# i2c_pullups.net
KiCad netlist of a schematic drawn in Altium Designer
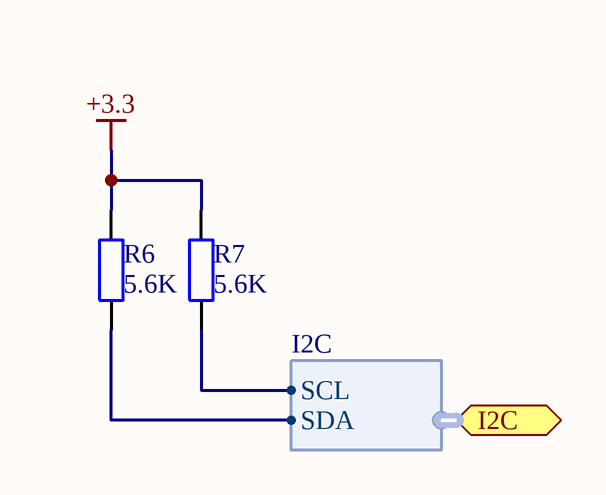
[diagram p0: i2c pullups.SchDoc]

(export (version "E")
  (design (tool "Eeschema 10.0.6"))
  (components
    (comp (ref "R6")
      (value "5.6K")
      (footprint "R0603")
      (description "Resistor")
      (fields (field (name "Comment") "Res2") (field (name "PUBLISHER") "Altium Limited"))
      (libsource (lib "Miscellaneous Devices") (part "Res2"))
    )
    (comp (ref "R7")
      (value "5.6K")
      (footprint "R0603")
      (description "Resistor")
      (fields (field (name "Comment") "Res2") (field (name "PUBLISHER") "Altium Limited"))
      (libsource (lib "Miscellaneous Devices") (part "Res2"))
    )
  )
  (nets
    (net (code "2") (name "+3.3") (class "Default")
      (node (ref "R6") (pin "2") (pinfunction "2_2") (pintype "passive"))
      (node (ref "R7") (pin "2") (pinfunction "2_2") (pintype "passive"))
    )
    (net (code "3") (name "/SCL") (class "Default")
      (node (ref "R7") (pin "1") (pinfunction "1_1") (pintype "passive"))
    )
    (net (code "4") (name "/SDA") (class "Default")
      (node (ref "R6") (pin "1") (pinfunction "1_1") (pintype "passive"))
    )
  )
)
